# sensor.net
KiCad netlist of a schematic drawn in EAGLE
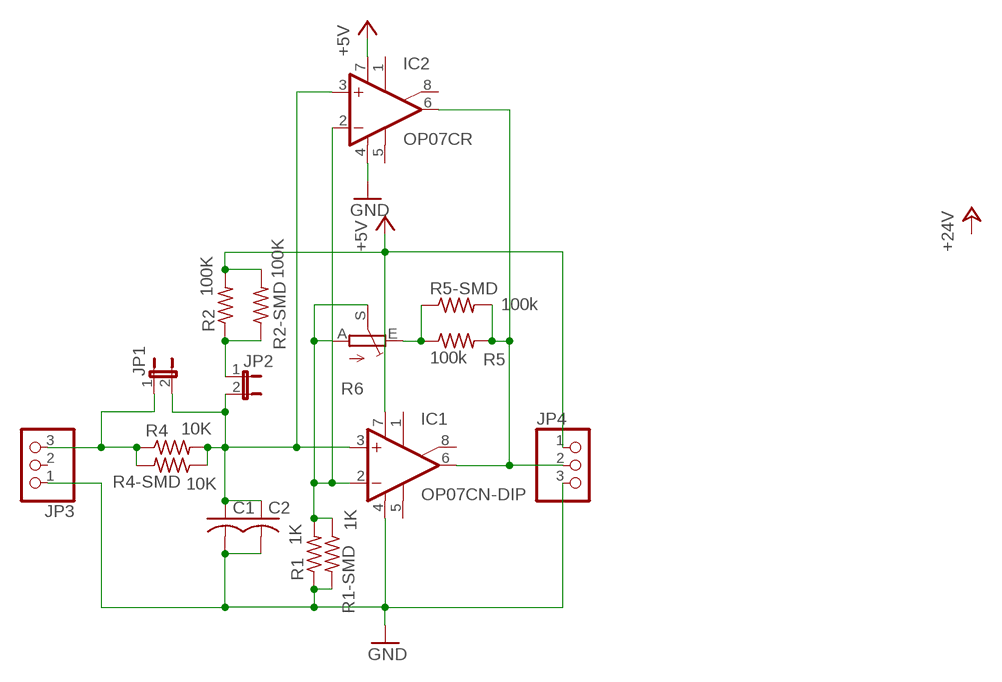
[diagram p0: schematic, sheet 1]

(export (version "E")
  (design (tool "Eeschema 10.0.6"))
  (components
    (comp (ref "C1")
      (value "C-US025-030X050")
      (footprint "eagle-import:C025-030X050")
      (libsource (lib "eagle-import") (part "C-US025-030X050"))
    )
    (comp (ref "C2")
      (value "C-USC0805")
      (footprint "eagle-import:C0805")
      (libsource (lib "eagle-import") (part "C-USC0805"))
    )
    (comp (ref "IC1")
      (value "OP07CN-DIP")
      (footprint "eagle-import:DIL08")
      (libsource (lib "eagle-import") (part "OP07NC"))
    )
    (comp (ref "IC2")
      (value "OP07CR")
      (footprint "eagle-import:SO08")
      (libsource (lib "eagle-import") (part "OP07RC"))
    )
    (comp (ref "JP1")
      (value "JP1E")
      (footprint "eagle-import:JP1")
      (libsource (lib "eagle-import") (part "JP1E"))
    )
    (comp (ref "JP2")
      (value "JP1E")
      (footprint "eagle-import:JP1")
      (libsource (lib "eagle-import") (part "JP1E"))
    )
    (comp (ref "JP3")
      (value "PINHD-1X3")
      (footprint "eagle-import:1X03")
      (libsource (lib "eagle-import") (part "PINHD-1X3"))
    )
    (comp (ref "JP4")
      (value "PINHD-1X3")
      (footprint "eagle-import:1X03")
      (libsource (lib "eagle-import") (part "PINHD-1X3"))
    )
    (comp (ref "R1")
      (value "1K")
      (footprint "eagle-import:0204_5")
      (libsource (lib "eagle-import") (part "R-US_0204/5"))
    )
    (comp (ref "R1-SMD")
      (value "1K")
      (footprint "eagle-import:R0805")
      (libsource (lib "eagle-import") (part "R-US_R0805"))
    )
    (comp (ref "R2")
      (value "100K")
      (footprint "eagle-import:0204_5")
      (libsource (lib "eagle-import") (part "R-US_0204/5"))
    )
    (comp (ref "R2-SMD")
      (value "100K")
      (footprint "eagle-import:R0805")
      (libsource (lib "eagle-import") (part "R-US_R0805"))
    )
    (comp (ref "R4")
      (value "10K")
      (footprint "eagle-import:0204_5")
      (libsource (lib "eagle-import") (part "R-US_0204/5"))
    )
    (comp (ref "R4-SMD")
      (value "10K")
      (footprint "eagle-import:R0805")
      (libsource (lib "eagle-import") (part "R-US_R0805"))
    )
    (comp (ref "R5")
      (value "100k")
      (footprint "eagle-import:0204_5")
      (libsource (lib "eagle-import") (part "R-US_0204/5"))
    )
    (comp (ref "R5-SMD")
      (value "100k")
      (footprint "eagle-import:R0805")
      (libsource (lib "eagle-import") (part "R-US_R0805"))
    )
    (comp (ref "R6")
      (value "TRIM_EU-B64Y")
      (footprint "eagle-import:B64Y")
      (libsource (lib "eagle-import") (part "TRIM_EU-B64Y"))
    )
  )
  (nets
    (net (code "1") (name "+5V") (class "Default")
      (node (ref "IC1") (pin "7") (pinfunction "V+_7") (pintype "power_in"))
      (node (ref "IC2") (pin "7") (pinfunction "V+_7") (pintype "power_in"))
      (node (ref "JP4") (pin "1") (pinfunction "1_1") (pintype "passive"))
      (node (ref "R2") (pin "2") (pinfunction "2_2") (pintype "passive"))
      (node (ref "R2-SMD") (pin "2") (pinfunction "2_2") (pintype "passive"))
    )
    (net (code "3") (name "GND") (class "Default")
      (node (ref "C1") (pin "2") (pinfunction "2_2") (pintype "passive"))
      (node (ref "C2") (pin "2") (pinfunction "2_2") (pintype "passive"))
      (node (ref "IC1") (pin "4") (pinfunction "V-_4") (pintype "power_in"))
      (node (ref "IC2") (pin "4") (pinfunction "V-_4") (pintype "power_in"))
      (node (ref "JP3") (pin "1") (pinfunction "1_1") (pintype "passive"))
      (node (ref "JP4") (pin "3") (pinfunction "3_3") (pintype "passive"))
      (node (ref "R1") (pin "1") (pinfunction "1_1") (pintype "passive"))
      (node (ref "R1-SMD") (pin "2") (pinfunction "2_2") (pintype "passive"))
    )
    (net (code "4") (name "Net-(IC1-+IN)") (class "Default")
      (node (ref "C1") (pin "1") (pinfunction "1_1") (pintype "passive"))
      (node (ref "C2") (pin "1") (pinfunction "1_1") (pintype "passive"))
      (node (ref "IC1") (pin "3") (pinfunction "+IN_3") (pintype "input"))
      (node (ref "IC2") (pin "3") (pinfunction "+IN_3") (pintype "input"))
      (node (ref "JP1") (pin "2") (pinfunction "2_2") (pintype "passive"))
      (node (ref "JP2") (pin "2") (pinfunction "2_2") (pintype "passive"))
      (node (ref "R4") (pin "2") (pinfunction "2_2") (pintype "passive"))
      (node (ref "R4-SMD") (pin "1") (pinfunction "1_1") (pintype "passive"))
    )
    (net (code "5") (name "Net-(IC1--IN)") (class "Default")
      (node (ref "IC1") (pin "2") (pinfunction "-IN_2") (pintype "input"))
      (node (ref "IC2") (pin "2") (pinfunction "-IN_2") (pintype "input"))
      (node (ref "R1") (pin "2") (pinfunction "2_2") (pintype "passive"))
      (node (ref "R1-SMD") (pin "1") (pinfunction "1_1") (pintype "passive"))
      (node (ref "R6") (pin "A") (pinfunction "A_A") (pintype "passive"))
      (node (ref "R6") (pin "S") (pinfunction "S_S") (pintype "passive"))
    )
    (net (code "6") (name "Net-(IC1-OUT)") (class "Default")
      (node (ref "IC1") (pin "6") (pinfunction "OUT_6") (pintype "output"))
      (node (ref "IC2") (pin "6") (pinfunction "OUT_6") (pintype "output"))
      (node (ref "JP4") (pin "2") (pinfunction "2_2") (pintype "passive"))
      (node (ref "R5") (pin "2") (pinfunction "2_2") (pintype "passive"))
      (node (ref "R5-SMD") (pin "2") (pinfunction "2_2") (pintype "passive"))
    )
    (net (code "7") (name "Net-(JP1-Pad1)") (class "Default")
      (node (ref "JP1") (pin "1") (pinfunction "1_1") (pintype "passive"))
      (node (ref "JP3") (pin "3") (pinfunction "3_3") (pintype "passive"))
      (node (ref "R4") (pin "1") (pinfunction "1_1") (pintype "passive"))
      (node (ref "R4-SMD") (pin "2") (pinfunction "2_2") (pintype "passive"))
    )
    (net (code "8") (name "Net-(JP2-Pad1)") (class "Default")
      (node (ref "JP2") (pin "1") (pinfunction "1_1") (pintype "passive"))
      (node (ref "R2") (pin "1") (pinfunction "1_1") (pintype "passive"))
      (node (ref "R2-SMD") (pin "1") (pinfunction "1_1") (pintype "passive"))
    )
    (net (code "9") (name "Net-(R5-Pad1)") (class "Default")
      (node (ref "R5") (pin "1") (pinfunction "1_1") (pintype "passive"))
      (node (ref "R5-SMD") (pin "1") (pinfunction "1_1") (pintype "passive"))
      (node (ref "R6") (pin "E") (pinfunction "E_E") (pintype "passive"))
    )
    (net (code "10") (name "unconnected-(IC1-ON1-Pad1)") (class "Default")
      (node (ref "IC1") (pin "1") (pinfunction "ON1_1") (pintype "passive"))
    )
    (net (code "11") (name "unconnected-(IC1-ON2-Pad8)") (class "Default")
      (node (ref "IC1") (pin "8") (pinfunction "ON2_8") (pintype "passive"))
    )
    (net (code "12") (name "unconnected-(IC1-OPT-Pad5)") (class "Default")
      (node (ref "IC1") (pin "5") (pinfunction "OPT_5") (pintype "passive"))
    )
    (net (code "13") (name "unconnected-(IC2-ON1-Pad1)") (class "Default")
      (node (ref "IC2") (pin "1") (pinfunction "ON1_1") (pintype "passive"))
    )
    (net (code "14") (name "unconnected-(IC2-ON2-Pad8)") (class "Default")
      (node (ref "IC2") (pin "8") (pinfunction "ON2_8") (pintype "passive"))
    )
    (net (code "15") (name "unconnected-(IC2-OPT-Pad5)") (class "Default")
      (node (ref "IC2") (pin "5") (pinfunction "OPT_5") (pintype "passive"))
    )
    (net (code "16") (name "unconnected-(JP3-Pad2)") (class "Default")
      (node (ref "JP3") (pin "2") (pinfunction "2_2") (pintype "passive"))
    )
  )
)
